# voltage_dividers.net
KiCad netlist of a schematic drawn in EAGLE
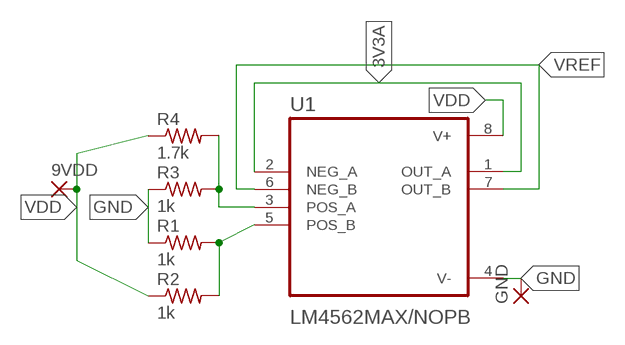
[diagram p0: schematic, sheet 1]

(export (version "E")
  (design (tool "Eeschema 10.0.6"))
  (components
    (comp (ref "9VDD")
      (value "SMD2")
      (footprint "eagle-import:SMD1,27-2,54")
      (libsource (lib "eagle-import") (part "SMD2"))
    )
    (comp (ref "GND")
      (value "SMD2")
      (footprint "eagle-import:SMD1,27-2,54")
      (libsource (lib "eagle-import") (part "SMD2"))
    )
    (comp (ref "R1")
      (value "1k")
      (footprint "eagle-import:R0402")
      (libsource (lib "eagle-import") (part "R-US_R0402"))
    )
    (comp (ref "R2")
      (value "1k")
      (footprint "eagle-import:R0402")
      (libsource (lib "eagle-import") (part "R-US_R0402"))
    )
    (comp (ref "R3")
      (value "1k")
      (footprint "eagle-import:R0402")
      (libsource (lib "eagle-import") (part "R-US_R0402"))
    )
    (comp (ref "R4")
      (value "1.7k")
      (footprint "eagle-import:R0402")
      (libsource (lib "eagle-import") (part "R-US_R0402"))
    )
    (comp (ref "U1")
      (value "LM4562MAX/NOPB")
      (footprint "eagle-import:SOIC127P599X175-8N")
      (fields (field (name "MF") "Texas Instruments"))
      (libsource (lib "eagle-import") (part "LM4562MAX/NOPB"))
    )
  )
  (nets
    (net (code "1") (name "3V3A") (class "Default")
      (node (ref "U1") (pin "1") (pinfunction "OUT_A_1") (pintype "output"))
      (node (ref "U1") (pin "2") (pinfunction "NEG_A_2") (pintype "input"))
    )
    (net (code "2") (name "GND") (class "Default")
      (node (ref "GND") (pin "1") (pinfunction "P_1") (pintype "passive"))
      (node (ref "R1") (pin "1") (pinfunction "1_1") (pintype "passive"))
      (node (ref "R3") (pin "1") (pinfunction "1_1") (pintype "passive"))
      (node (ref "U1") (pin "4") (pinfunction "V-_4") (pintype "power_in"))
    )
    (net (code "3") (name "Net-(U1-POS_A)") (class "Default")
      (node (ref "R3") (pin "2") (pinfunction "2_2") (pintype "passive"))
      (node (ref "R4") (pin "2") (pinfunction "2_2") (pintype "passive"))
      (node (ref "U1") (pin "3") (pinfunction "POS_A_3") (pintype "input"))
    )
    (net (code "4") (name "Net-(U1-POS_B)") (class "Default")
      (node (ref "R1") (pin "2") (pinfunction "2_2") (pintype "passive"))
      (node (ref "R2") (pin "2") (pinfunction "2_2") (pintype "passive"))
      (node (ref "U1") (pin "5") (pinfunction "POS_B_5") (pintype "input"))
    )
    (net (code "5") (name "VDD") (class "Default")
      (node (ref "9VDD") (pin "1") (pinfunction "P_1") (pintype "passive"))
      (node (ref "R2") (pin "1") (pinfunction "1_1") (pintype "passive"))
      (node (ref "R4") (pin "1") (pinfunction "1_1") (pintype "passive"))
      (node (ref "U1") (pin "8") (pinfunction "V+_8") (pintype "power_in"))
    )
    (net (code "6") (name "VREF") (class "Default")
      (node (ref "U1") (pin "6") (pinfunction "NEG_B_6") (pintype "input"))
      (node (ref "U1") (pin "7") (pinfunction "OUT_B_7") (pintype "output"))
    )
  )
)
